# TMC2130.net
KiCad netlist of a schematic drawn in Altium Designer
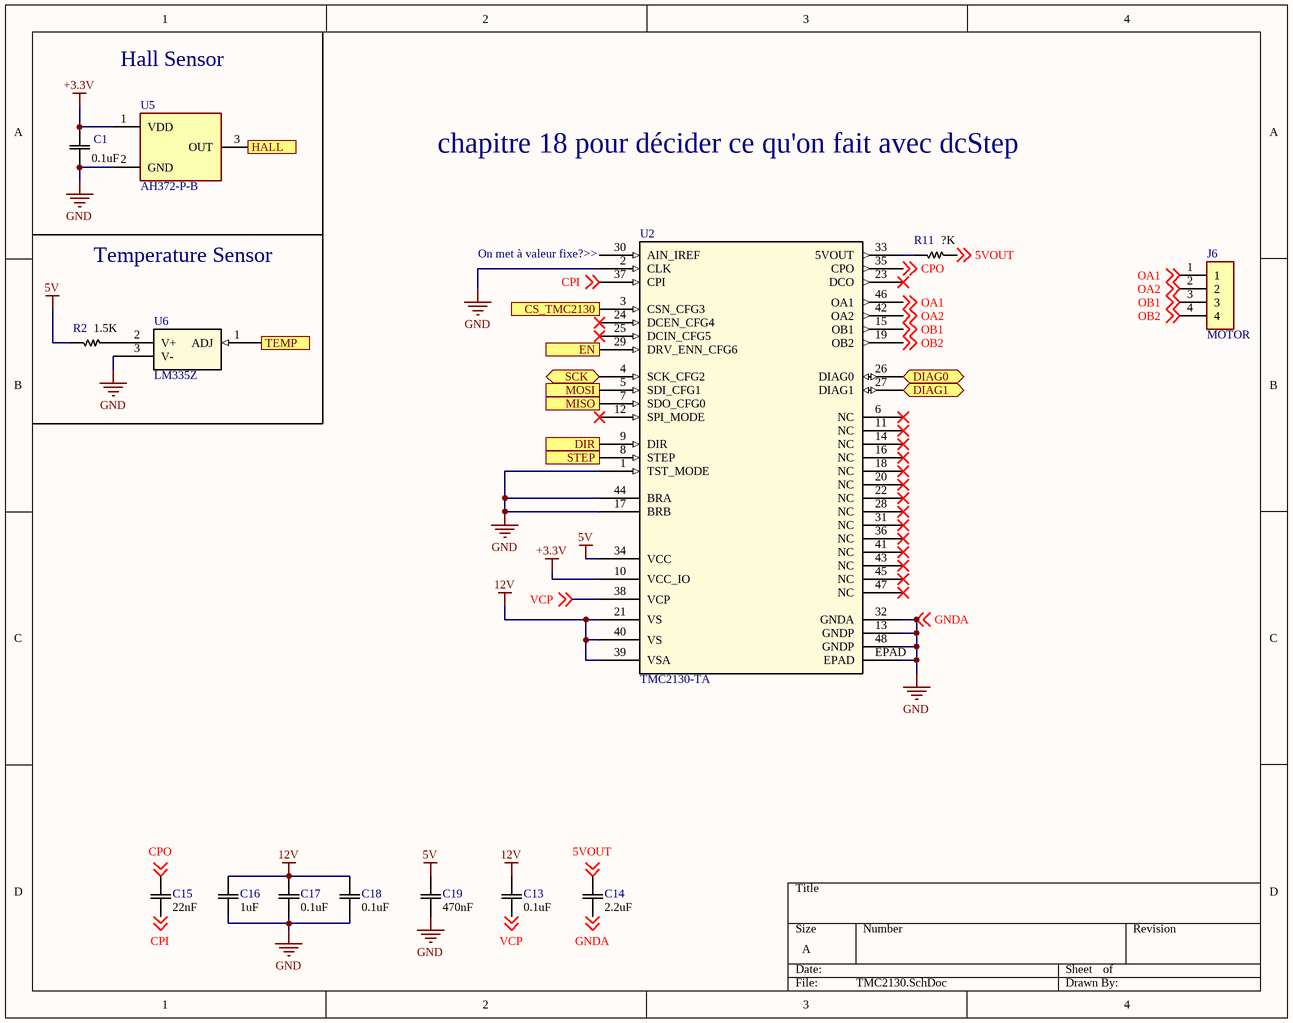
[diagram p0: TMC2130.SchDoc]

(export (version "E")
  (design (tool "Eeschema 10.0.6"))
  (components
    (comp (ref "C1")
      (value "0.1uF")
      (footprint "0603")
      (description "Capacitor SMD 1206")
      (fields
        (field (name "MANUFACTURER_PART_NUMBER") "12065A820JAT2A")
        (field (name "Comment") "Capacitor 1206")
        (field (name "COPYRIGHT") "Copyright (C) 2018 Accelerated Designs. All rights reserved")
      )
      (libsource (lib "Schematic_Emile") (part "Capacitor 1206"))
    )
    (comp (ref "C13")
      (value "0.1uF")
      (footprint "0603")
      (description "Capacitor SMD 1206")
      (fields
        (field (name "MANUFACTURER_PART_NUMBER") "12065A820JAT2A")
        (field (name "Comment") "Capacitor 1206")
        (field (name "COPYRIGHT") "Copyright (C) 2018 Accelerated Designs. All rights reserved")
      )
      (libsource (lib "Schematic_Emile") (part "Capacitor 1206"))
    )
    (comp (ref "C14")
      (value "2.2uF")
      (footprint "0603")
      (description "Capacitor SMD 1206")
      (fields
        (field (name "MANUFACTURER_PART_NUMBER") "12065A820JAT2A")
        (field (name "Comment") "Capacitor 1206")
        (field (name "COPYRIGHT") "Copyright (C) 2018 Accelerated Designs. All rights reserved")
      )
      (libsource (lib "Schematic_Emile") (part "Capacitor 1206"))
    )
    (comp (ref "C15")
      (value "22nF")
      (footprint "0603")
      (description "Capacitor SMD 1206")
      (fields
        (field (name "MANUFACTURER_PART_NUMBER") "12065A820JAT2A")
        (field (name "Comment") "Capacitor 1206")
        (field (name "COPYRIGHT") "Copyright (C) 2018 Accelerated Designs. All rights reserved")
      )
      (libsource (lib "Schematic_Emile") (part "Capacitor 1206"))
    )
    (comp (ref "C16")
      (value "1uF")
      (footprint "0603")
      (description "Capacitor SMD 1206")
      (fields
        (field (name "MANUFACTURER_PART_NUMBER") "12065A820JAT2A")
        (field (name "Comment") "Capacitor 1206")
        (field (name "COPYRIGHT") "Copyright (C) 2018 Accelerated Designs. All rights reserved")
      )
      (libsource (lib "Schematic_Emile") (part "Capacitor 1206"))
    )
    (comp (ref "C17")
      (value "0.1uF")
      (footprint "0603")
      (description "Capacitor SMD 1206")
      (fields
        (field (name "MANUFACTURER_PART_NUMBER") "12065A820JAT2A")
        (field (name "Comment") "Capacitor 1206")
        (field (name "COPYRIGHT") "Copyright (C) 2018 Accelerated Designs. All rights reserved")
      )
      (libsource (lib "Schematic_Emile") (part "Capacitor 1206"))
    )
    (comp (ref "C18")
      (value "0.1uF")
      (footprint "0603")
      (description "Capacitor SMD 1206")
      (fields
        (field (name "MANUFACTURER_PART_NUMBER") "12065A820JAT2A")
        (field (name "Comment") "Capacitor 1206")
        (field (name "COPYRIGHT") "Copyright (C) 2018 Accelerated Designs. All rights reserved")
      )
      (libsource (lib "Schematic_Emile") (part "Capacitor 1206"))
    )
    (comp (ref "C19")
      (value "470nF")
      (footprint "0603")
      (description "Capacitor SMD 1206")
      (fields
        (field (name "MANUFACTURER_PART_NUMBER") "12065A820JAT2A")
        (field (name "Comment") "Capacitor 1206")
        (field (name "COPYRIGHT") "Copyright (C) 2018 Accelerated Designs. All rights reserved")
      )
      (libsource (lib "Schematic_Emile") (part "Capacitor 1206"))
    )
    (comp (ref "J6")
      (value "MOTOR")
      (footprint "JST 4POS 2.5mm 90°")
      (description "Connector")
      (fields
        (field (name "MANUFACTURER_PART_NUMBER") "S4B-XH-A(LF)(SN)")
        (field (name "RS PART NUMBER") "8201589P")
      )
      (libsource (lib "Schematic_Emile") (part "JST 4POS"))
    )
    (comp (ref "R2")
      (value "1.5K")
      (footprint "0603")
      (description "Resistor 1206 SMD")
      (fields
        (field (name "MANUFACTURER_PART_NUMBER") "ERJ8CWFR024V")
        (field (name "Comment") "Resistor 1206")
        (field (name "COPYRIGHT") "Copyright (C) 2018 Accelerated Designs. All rights reserved")
      )
      (libsource (lib "Schematic_Emile") (part "Resistor 1206"))
    )
    (comp (ref "R11")
      (value "?K")
      (footprint "0603")
      (description "Resistor 1206 SMD")
      (fields
        (field (name "MANUFACTURER_PART_NUMBER") "ERJ8CWFR024V")
        (field (name "Comment") "Resistor 1206")
        (field (name "COPYRIGHT") "Copyright (C) 2018 Accelerated Designs. All rights reserved")
      )
      (libsource (lib "Schematic_Emile") (part "Resistor 1206"))
    )
    (comp (ref "U2")
      (value "TMC2130-TA")
      (footprint "eTQFP48_9x9")
      (description "Motor Driver TMC2130")
      (fields (field (name "COPYRIGHT") "Copyright (C) 2016 Accelerated Designs. All rights reserved"))
      (libsource (lib "Schematic_Emile") (part "TMC2130-TA"))
    )
    (comp (ref "U5")
      (value "AH372-P-B")
      (footprint "SamacSys:AH372PB")
      (description "Hall Sensor")
      (fields (field (name "MOUSER PART NUMBER") "621-AH372-P-B") (field (name "RS PART NUMBER") "1333361P"))
      (libsource (lib "Schematic_Emile") (part "AH372-P-B"))
    )
    (comp (ref "U6")
      (value "LM335Z")
      (footprint "TO92")
      (description "Temperature Sensor")
      (fields (field (name "COPYRIGHT") "Copyright (C) 2018 Accelerated Designs. All rights reserved"))
      (libsource (lib "Schematic_Emile") (part "LM335Z"))
    )
  )
  (nets
    (net (code "1") (name "+3.3V") (class "Default")
      (node (ref "C1") (pin "2") (pinfunction "2_2") (pintype "passive"))
      (node (ref "U2") (pin "10") (pinfunction "VCC_IO_10") (pintype "power_in"))
      (node (ref "U5") (pin "1") (pinfunction "VDD_1") (pintype "passive"))
    )
    (net (code "2") (name "/CS_TMC2130") (class "Default")
      (node (ref "U2") (pin "3") (pinfunction "CSN_CFG3_3") (pintype "input"))
    )
    (net (code "3") (name "/DIAG0") (class "Default")
      (node (ref "U2") (pin "26") (pinfunction "DIAG0_26") (pintype "bidirectional"))
    )
    (net (code "4") (name "/DIAG1") (class "Default")
      (node (ref "U2") (pin "27") (pinfunction "DIAG1_27") (pintype "bidirectional"))
    )
    (net (code "5") (name "/DIR") (class "Default")
      (node (ref "U2") (pin "9") (pinfunction "DIR_9") (pintype "input"))
    )
    (net (code "6") (name "/EN") (class "Default")
      (node (ref "U2") (pin "29") (pinfunction "DRV_ENN_CFG6_29") (pintype "input"))
    )
    (net (code "7") (name "/HALL") (class "Default")
      (node (ref "U5") (pin "3") (pinfunction "OUT_3") (pintype "passive"))
    )
    (net (code "8") (name "/MISO") (class "Default")
      (node (ref "U2") (pin "7") (pinfunction "SDO_CFG0_7") (pintype "input"))
    )
    (net (code "9") (name "/MOSI") (class "Default")
      (node (ref "U2") (pin "5") (pinfunction "SDI_CFG1_5") (pintype "input"))
    )
    (net (code "10") (name "/SCK") (class "Default")
      (node (ref "U2") (pin "4") (pinfunction "SCK_CFG2_4") (pintype "input"))
    )
    (net (code "11") (name "/STEP") (class "Default")
      (node (ref "U2") (pin "8") (pinfunction "STEP_8") (pintype "input"))
    )
    (net (code "12") (name "/TEMP") (class "Default")
      (node (ref "U6") (pin "1") (pinfunction "ADJ_1") (pintype "input"))
    )
    (net (code "13") (name "5V") (class "Default")
      (node (ref "C19") (pin "2") (pinfunction "2_2") (pintype "passive"))
      (node (ref "R2") (pin "1") (pinfunction "1_1") (pintype "passive"))
      (node (ref "U2") (pin "34") (pinfunction "VCC_34") (pintype "power_in"))
    )
    (net (code "14") (name "5VOUT") (class "Default")
      (node (ref "C14") (pin "2") (pinfunction "2_2") (pintype "passive"))
      (node (ref "R11") (pin "2") (pinfunction "2_2") (pintype "passive"))
    )
    (net (code "15") (name "12V") (class "Default")
      (node (ref "C13") (pin "2") (pinfunction "2_2") (pintype "passive"))
      (node (ref "C16") (pin "2") (pinfunction "2_2") (pintype "passive"))
      (node (ref "C17") (pin "2") (pinfunction "2_2") (pintype "passive"))
      (node (ref "C18") (pin "2") (pinfunction "2_2") (pintype "passive"))
      (node (ref "U2") (pin "21") (pinfunction "VS_21") (pintype "power_in"))
      (node (ref "U2") (pin "39") (pinfunction "VSA_39") (pintype "power_in"))
      (node (ref "U2") (pin "40") (pinfunction "VS_40") (pintype "power_in"))
    )
    (net (code "16") (name "CPI") (class "Default")
      (node (ref "C15") (pin "1") (pinfunction "1_1") (pintype "passive"))
      (node (ref "U2") (pin "37") (pinfunction "CPI_37") (pintype "input"))
    )
    (net (code "17") (name "CPO") (class "Default")
      (node (ref "C15") (pin "2") (pinfunction "2_2") (pintype "passive"))
      (node (ref "U2") (pin "35") (pinfunction "CPO_35") (pintype "output"))
    )
    (net (code "18") (name "GND") (class "Default")
      (node (ref "C1") (pin "1") (pinfunction "1_1") (pintype "passive"))
      (node (ref "C14") (pin "1") (pinfunction "1_1") (pintype "passive"))
      (node (ref "C16") (pin "1") (pinfunction "1_1") (pintype "passive"))
      (node (ref "C17") (pin "1") (pinfunction "1_1") (pintype "passive"))
      (node (ref "C18") (pin "1") (pinfunction "1_1") (pintype "passive"))
      (node (ref "C19") (pin "1") (pinfunction "1_1") (pintype "passive"))
      (node (ref "U2") (pin "1") (pinfunction "TST_MODE_1") (pintype "input"))
      (node (ref "U2") (pin "13") (pinfunction "GNDP_13") (pintype "power_in"))
      (node (ref "U2") (pin "17") (pinfunction "BRB_17") (pintype "passive"))
      (node (ref "U2") (pin "2") (pinfunction "CLK_2") (pintype "input"))
      (node (ref "U2") (pin "32") (pinfunction "GNDA_32") (pintype "power_in"))
      (node (ref "U2") (pin "44") (pinfunction "BRA_44") (pintype "passive"))
      (node (ref "U2") (pin "48") (pinfunction "GNDP_48") (pintype "power_in"))
      (node (ref "U2") (pin "EPAD") (pinfunction "EPAD_EPAD") (pintype "passive"))
      (node (ref "U5") (pin "2") (pinfunction "GND_2") (pintype "passive"))
      (node (ref "U6") (pin "3") (pinfunction "V-_3") (pintype "power_in"))
    )
    (net (code "19") (name "Net-(U2-5VOUT)") (class "Default")
      (node (ref "R11") (pin "1") (pinfunction "1_1") (pintype "passive"))
      (node (ref "U2") (pin "33") (pinfunction "5VOUT_33") (pintype "output"))
    )
    (net (code "20") (name "Net-(U6-V+)") (class "Default")
      (node (ref "R2") (pin "2") (pinfunction "2_2") (pintype "passive"))
      (node (ref "U6") (pin "2") (pinfunction "V+_2") (pintype "power_in"))
    )
    (net (code "21") (name "OA1") (class "Default")
      (node (ref "J6") (pin "1") (pinfunction "1_1") (pintype "passive"))
      (node (ref "U2") (pin "46") (pinfunction "OA1_46") (pintype "output"))
    )
    (net (code "22") (name "OA2") (class "Default")
      (node (ref "J6") (pin "2") (pinfunction "2_2") (pintype "passive"))
      (node (ref "U2") (pin "42") (pinfunction "OA2_42") (pintype "output"))
    )
    (net (code "23") (name "OB1") (class "Default")
      (node (ref "J6") (pin "3") (pinfunction "3_3") (pintype "passive"))
      (node (ref "U2") (pin "15") (pinfunction "OB1_15") (pintype "output"))
    )
    (net (code "24") (name "OB2") (class "Default")
      (node (ref "J6") (pin "4") (pinfunction "4_4") (pintype "passive"))
      (node (ref "U2") (pin "19") (pinfunction "OB2_19") (pintype "output"))
    )
    (net (code "25") (name "VCP") (class "Default")
      (node (ref "C13") (pin "1") (pinfunction "1_1") (pintype "passive"))
      (node (ref "U2") (pin "38") (pinfunction "VCP_38") (pintype "power_in"))
    )
    (net (code "26") (name "unconnected-(U2-AIN_IREF-Pad30)") (class "Default")
      (node (ref "U2") (pin "30") (pinfunction "AIN_IREF_30") (pintype "input"))
    )
    (net (code "27") (name "unconnected-(U2-DCEN_CFG4-Pad24)") (class "Default")
      (node (ref "U2") (pin "24") (pinfunction "DCEN_CFG4_24") (pintype "input+no_connect"))
    )
    (net (code "28") (name "unconnected-(U2-DCIN_CFG5-Pad25)") (class "Default")
      (node (ref "U2") (pin "25") (pinfunction "DCIN_CFG5_25") (pintype "input+no_connect"))
    )
    (net (code "29") (name "unconnected-(U2-DCO-Pad23)") (class "Default")
      (node (ref "U2") (pin "23") (pinfunction "DCO_23") (pintype "output+no_connect"))
    )
    (net (code "30") (name "unconnected-(U2-NC-Pad6)") (class "Default")
      (node (ref "U2") (pin "6") (pinfunction "NC_6") (pintype "passive+no_connect"))
    )
    (net (code "31") (name "unconnected-(U2-NC-Pad11)") (class "Default")
      (node (ref "U2") (pin "11") (pinfunction "NC_11") (pintype "passive+no_connect"))
    )
    (net (code "32") (name "unconnected-(U2-NC-Pad14)") (class "Default")
      (node (ref "U2") (pin "14") (pinfunction "NC_14") (pintype "passive+no_connect"))
    )
    (net (code "33") (name "unconnected-(U2-NC-Pad16)") (class "Default")
      (node (ref "U2") (pin "16") (pinfunction "NC_16") (pintype "passive+no_connect"))
    )
    (net (code "34") (name "unconnected-(U2-NC-Pad18)") (class "Default")
      (node (ref "U2") (pin "18") (pinfunction "NC_18") (pintype "passive+no_connect"))
    )
    (net (code "35") (name "unconnected-(U2-NC-Pad20)") (class "Default")
      (node (ref "U2") (pin "20") (pinfunction "NC_20") (pintype "passive+no_connect"))
    )
    (net (code "36") (name "unconnected-(U2-NC-Pad22)") (class "Default")
      (node (ref "U2") (pin "22") (pinfunction "NC_22") (pintype "passive+no_connect"))
    )
    (net (code "37") (name "unconnected-(U2-NC-Pad28)") (class "Default")
      (node (ref "U2") (pin "28") (pinfunction "NC_28") (pintype "passive+no_connect"))
    )
    (net (code "38") (name "unconnected-(U2-NC-Pad31)") (class "Default")
      (node (ref "U2") (pin "31") (pinfunction "NC_31") (pintype "passive+no_connect"))
    )
    (net (code "39") (name "unconnected-(U2-NC-Pad36)") (class "Default")
      (node (ref "U2") (pin "36") (pinfunction "NC_36") (pintype "passive+no_connect"))
    )
    (net (code "40") (name "unconnected-(U2-NC-Pad41)") (class "Default")
      (node (ref "U2") (pin "41") (pinfunction "NC_41") (pintype "passive+no_connect"))
    )
    (net (code "41") (name "unconnected-(U2-NC-Pad43)") (class "Default")
      (node (ref "U2") (pin "43") (pinfunction "NC_43") (pintype "passive+no_connect"))
    )
    (net (code "42") (name "unconnected-(U2-NC-Pad45)") (class "Default")
      (node (ref "U2") (pin "45") (pinfunction "NC_45") (pintype "passive+no_connect"))
    )
    (net (code "43") (name "unconnected-(U2-NC-Pad47)") (class "Default")
      (node (ref "U2") (pin "47") (pinfunction "NC_47") (pintype "passive+no_connect"))
    )
    (net (code "44") (name "unconnected-(U2-SPI_MODE-Pad12)") (class "Default")
      (node (ref "U2") (pin "12") (pinfunction "SPI_MODE_12") (pintype "input+no_connect"))
    )
  )
)
